# nrf_bridge.net
KiCad netlist of a schematic drawn in EAGLE
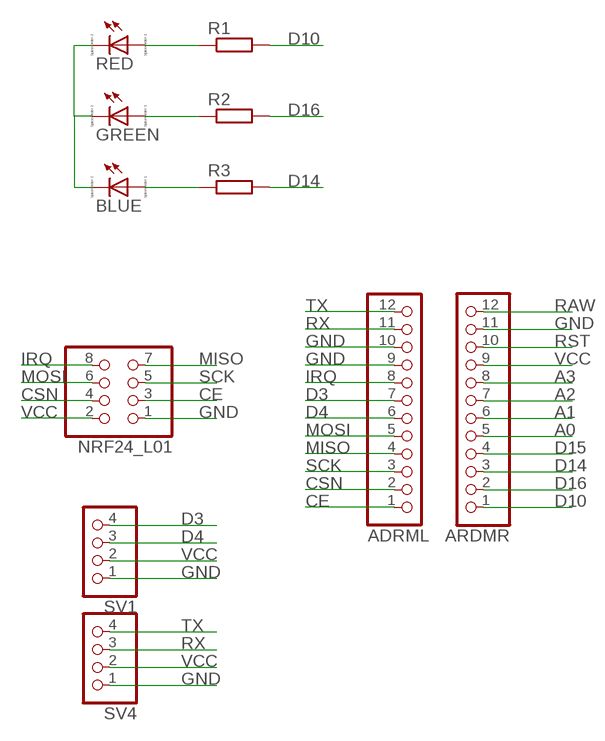
[diagram p0: schematic, sheet 1]

(export (version "E")
  (design (tool "Eeschema 10.0.6"))
  (components
    (comp (ref "ADRML")
      (value "PINHD-1X12_2.54-SMD")
      (footprint "eagle-import:1X12SMD")
      (libsource (lib "eagle-import") (part "PINHD-1X12_2.54-SMD"))
    )
    (comp (ref "ARDMR")
      (value "PINHD-1X12_2.54-SMD")
      (footprint "eagle-import:1X12SMD")
      (libsource (lib "eagle-import") (part "PINHD-1X12_2.54-SMD"))
    )
    (comp (ref "BLUE")
      (value "LED_ESML0603")
      (footprint "eagle-import:LED_SML0603")
      (libsource (lib "eagle-import") (part "LED_ESML0603"))
    )
    (comp (ref "GREEN")
      (value "LED_ESML0603")
      (footprint "eagle-import:LED_SML0603")
      (libsource (lib "eagle-import") (part "LED_ESML0603"))
    )
    (comp (ref "NRF24_L01")
      (value "PINHD-2X4_2.54-SMD")
      (footprint "eagle-import:2X04SMD")
      (libsource (lib "eagle-import") (part "PINHD-2X4_2.54-SMD"))
    )
    (comp (ref "R1")
      (value "R-EU_M0805")
      (footprint "eagle-import:M0805")
      (libsource (lib "eagle-import") (part "R-EU_M0805"))
    )
    (comp (ref "R2")
      (value "R-EU_M0805")
      (footprint "eagle-import:M0805")
      (libsource (lib "eagle-import") (part "R-EU_M0805"))
    )
    (comp (ref "R3")
      (value "R-EU_M0805")
      (footprint "eagle-import:M0805")
      (libsource (lib "eagle-import") (part "R-EU_M0805"))
    )
    (comp (ref "RED")
      (value "LED_ESML0603")
      (footprint "eagle-import:LED_SML0603")
      (libsource (lib "eagle-import") (part "LED_ESML0603"))
    )
    (comp (ref "SV1")
      (value "PINHD-1X4_2.54-SMD")
      (footprint "eagle-import:1X04SMD")
      (libsource (lib "eagle-import") (part "PINHD-1X4_2.54-SMD"))
    )
    (comp (ref "SV4")
      (value "PINHD-1X4_2.54-SMD")
      (footprint "eagle-import:1X04SMD")
      (libsource (lib "eagle-import") (part "PINHD-1X4_2.54-SMD"))
    )
  )
  (nets
    (net (code "1") (name "/A0") (class "Default")
      (node (ref "ARDMR") (pin "5") (pinfunction "5_5") (pintype "passive"))
    )
    (net (code "2") (name "/A1") (class "Default")
      (node (ref "ARDMR") (pin "6") (pinfunction "6_6") (pintype "passive"))
    )
    (net (code "3") (name "/A2") (class "Default")
      (node (ref "ARDMR") (pin "7") (pinfunction "7_7") (pintype "passive"))
    )
    (net (code "4") (name "/A3") (class "Default")
      (node (ref "ARDMR") (pin "8") (pinfunction "8_8") (pintype "passive"))
    )
    (net (code "5") (name "/CE") (class "Default")
      (node (ref "ADRML") (pin "1") (pinfunction "1_1") (pintype "passive"))
      (node (ref "NRF24_L01") (pin "3") (pinfunction "3_3") (pintype "passive"))
    )
    (net (code "6") (name "/CSN") (class "Default")
      (node (ref "ADRML") (pin "2") (pinfunction "2_2") (pintype "passive"))
      (node (ref "NRF24_L01") (pin "4") (pinfunction "4_4") (pintype "passive"))
    )
    (net (code "7") (name "/D3") (class "Default")
      (node (ref "ADRML") (pin "7") (pinfunction "7_7") (pintype "passive"))
      (node (ref "SV1") (pin "4") (pinfunction "4_4") (pintype "passive"))
    )
    (net (code "8") (name "/D4") (class "Default")
      (node (ref "ADRML") (pin "6") (pinfunction "6_6") (pintype "passive"))
      (node (ref "SV1") (pin "3") (pinfunction "3_3") (pintype "passive"))
    )
    (net (code "9") (name "/D10") (class "Default")
      (node (ref "ARDMR") (pin "1") (pinfunction "1_1") (pintype "passive"))
      (node (ref "R1") (pin "2") (pinfunction "2_2") (pintype "passive"))
    )
    (net (code "10") (name "/D14") (class "Default")
      (node (ref "ARDMR") (pin "3") (pinfunction "3_3") (pintype "passive"))
      (node (ref "R3") (pin "2") (pinfunction "2_2") (pintype "passive"))
    )
    (net (code "11") (name "/D15") (class "Default")
      (node (ref "ARDMR") (pin "4") (pinfunction "4_4") (pintype "passive"))
    )
    (net (code "12") (name "/D16") (class "Default")
      (node (ref "ARDMR") (pin "2") (pinfunction "2_2") (pintype "passive"))
      (node (ref "R2") (pin "2") (pinfunction "2_2") (pintype "passive"))
    )
    (net (code "13") (name "/GND") (class "Default")
      (node (ref "ADRML") (pin "10") (pinfunction "10_10") (pintype "passive"))
      (node (ref "ADRML") (pin "9") (pinfunction "9_9") (pintype "passive"))
      (node (ref "ARDMR") (pin "11") (pinfunction "11_11") (pintype "passive"))
      (node (ref "BLUE") (pin "C") (pinfunction "C_C") (pintype "passive"))
      (node (ref "GREEN") (pin "C") (pinfunction "C_C") (pintype "passive"))
      (node (ref "NRF24_L01") (pin "1") (pinfunction "1_1") (pintype "passive"))
      (node (ref "RED") (pin "C") (pinfunction "C_C") (pintype "passive"))
      (node (ref "SV1") (pin "1") (pinfunction "1_1") (pintype "passive"))
      (node (ref "SV4") (pin "1") (pinfunction "1_1") (pintype "passive"))
    )
    (net (code "14") (name "/IRQ") (class "Default")
      (node (ref "ADRML") (pin "8") (pinfunction "8_8") (pintype "passive"))
      (node (ref "NRF24_L01") (pin "8") (pinfunction "8_8") (pintype "passive"))
    )
    (net (code "15") (name "/MISO") (class "Default")
      (node (ref "ADRML") (pin "4") (pinfunction "4_4") (pintype "passive"))
      (node (ref "NRF24_L01") (pin "7") (pinfunction "7_7") (pintype "passive"))
    )
    (net (code "16") (name "/MOSI") (class "Default")
      (node (ref "ADRML") (pin "5") (pinfunction "5_5") (pintype "passive"))
      (node (ref "NRF24_L01") (pin "6") (pinfunction "6_6") (pintype "passive"))
    )
    (net (code "17") (name "/RAW") (class "Default")
      (node (ref "ARDMR") (pin "12") (pinfunction "12_12") (pintype "passive"))
    )
    (net (code "18") (name "/RST") (class "Default")
      (node (ref "ARDMR") (pin "10") (pinfunction "10_10") (pintype "passive"))
    )
    (net (code "19") (name "/RX") (class "Default")
      (node (ref "ADRML") (pin "11") (pinfunction "11_11") (pintype "passive"))
      (node (ref "SV4") (pin "3") (pinfunction "3_3") (pintype "passive"))
    )
    (net (code "20") (name "/SCK") (class "Default")
      (node (ref "ADRML") (pin "3") (pinfunction "3_3") (pintype "passive"))
      (node (ref "NRF24_L01") (pin "5") (pinfunction "5_5") (pintype "passive"))
    )
    (net (code "21") (name "/TX") (class "Default")
      (node (ref "ADRML") (pin "12") (pinfunction "12_12") (pintype "passive"))
      (node (ref "SV4") (pin "4") (pinfunction "4_4") (pintype "passive"))
    )
    (net (code "22") (name "/VCC") (class "Default")
      (node (ref "ARDMR") (pin "9") (pinfunction "9_9") (pintype "passive"))
      (node (ref "NRF24_L01") (pin "2") (pinfunction "2_2") (pintype "passive"))
      (node (ref "SV1") (pin "2") (pinfunction "2_2") (pintype "passive"))
      (node (ref "SV4") (pin "2") (pinfunction "2_2") (pintype "passive"))
    )
    (net (code "23") (name "Net-(BLUE-PadA)") (class "Default")
      (node (ref "BLUE") (pin "A") (pinfunction "A_A") (pintype "passive"))
      (node (ref "R3") (pin "1") (pinfunction "1_1") (pintype "passive"))
    )
    (net (code "24") (name "Net-(GREEN-PadA)") (class "Default")
      (node (ref "GREEN") (pin "A") (pinfunction "A_A") (pintype "passive"))
      (node (ref "R2") (pin "1") (pinfunction "1_1") (pintype "passive"))
    )
    (net (code "25") (name "Net-(R1-Pad1)") (class "Default")
      (node (ref "R1") (pin "1") (pinfunction "1_1") (pintype "passive"))
      (node (ref "RED") (pin "A") (pinfunction "A_A") (pintype "passive"))
    )
  )
)
